# OBDadapter.net
KiCad netlist of a schematic drawn in EAGLE
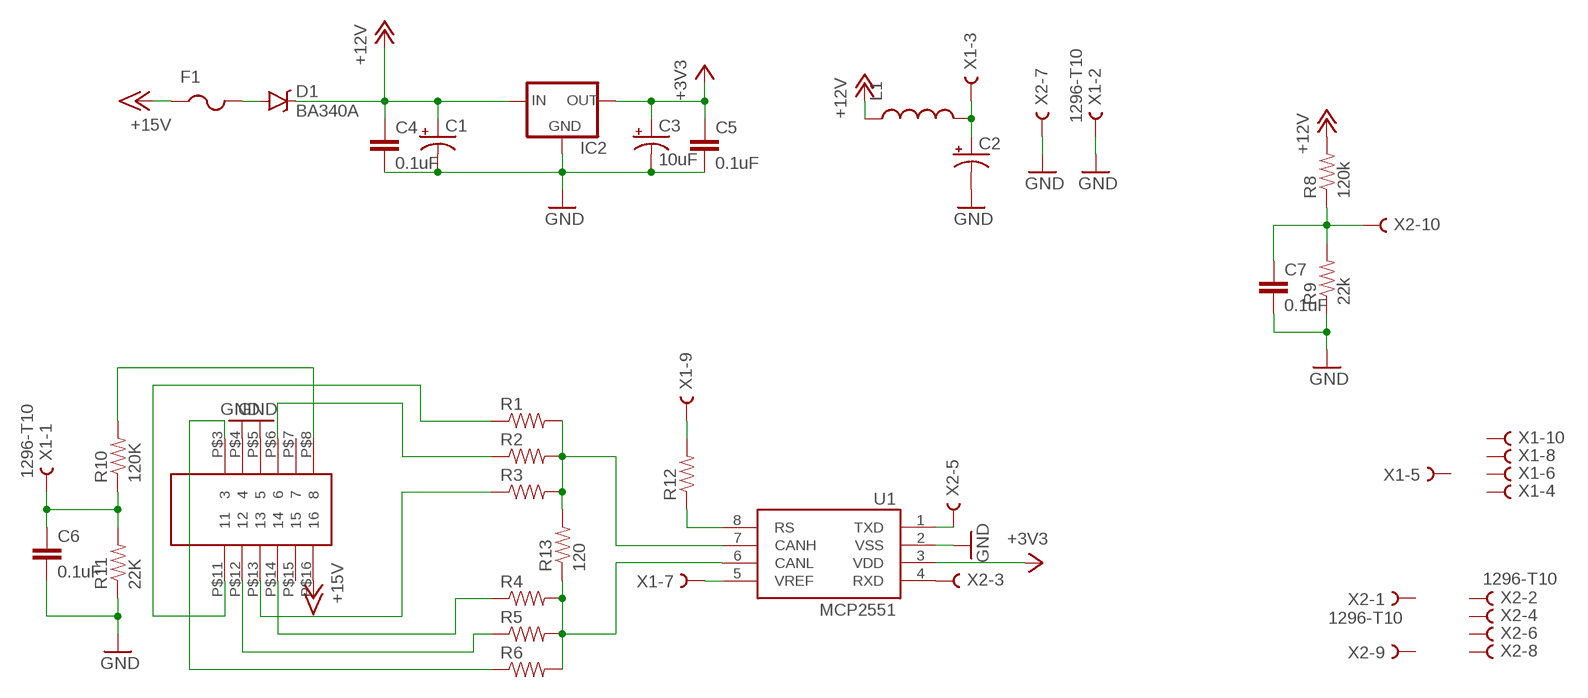
[diagram p0: schematic, sheet 1]

(export (version "E")
  (design (tool "Eeschema 10.0.6"))
  (components
    (comp (ref "C1")
      (value "CAP_POL3528-KIT")
      (footprint "eagle-import:EIA3528-KIT")
      (libsource (lib "eagle-import") (part "CAP_POL3528-KIT"))
    )
    (comp (ref "C2")
      (value "CAP_POL6032")
      (footprint "eagle-import:EIA6032")
      (libsource (lib "eagle-import") (part "CAP_POL6032"))
    )
    (comp (ref "C3")
      (value "10uF")
      (footprint "eagle-import:EIA3528")
      (libsource (lib "eagle-import") (part "10UF-20V-10%(TANT)"))
    )
    (comp (ref "C4")
      (value "0.1uF")
      (footprint "eagle-import:0603-CAP")
      (libsource (lib "eagle-import") (part "0.1UF-25V(+80/-20%)(0603)"))
    )
    (comp (ref "C5")
      (value "0.1uF")
      (footprint "eagle-import:0603-CAP")
      (libsource (lib "eagle-import") (part "0.1UF-25V(+80/-20%)(0603)"))
    )
    (comp (ref "C6")
      (value "0.1uF")
      (footprint "eagle-import:0603-CAP")
      (libsource (lib "eagle-import") (part "0.1UF-25V(+80/-20%)(0603)"))
    )
    (comp (ref "C7")
      (value "0.1uF")
      (footprint "eagle-import:0603-CAP")
      (libsource (lib "eagle-import") (part "0.1UF-25V(+80/-20%)(0603)"))
    )
    (comp (ref "D1")
      (value "BA340A")
      (footprint "eagle-import:SMA-DIODE")
      (libsource (lib "eagle-import") (part "B340A"))
    )
    (comp (ref "F1")
      (value "PTCFUSE-1206")
      (footprint "eagle-import:R1206")
      (libsource (lib "eagle-import") (part "PTCFUSE-1206"))
    )
    (comp (ref "IC2")
      (value "V_REG_78XXSOT89")
      (footprint "eagle-import:SOT89")
      (libsource (lib "eagle-import") (part "V_REG_78XXSOT89"))
    )
    (comp (ref "L1")
      (value "INDUCTOR1210")
      (footprint "eagle-import:1210")
      (libsource (lib "eagle-import") (part "INDUCTOR1210"))
    )
    (comp (ref "R1")
      (value "RESISTOR0805-RES")
      (footprint "eagle-import:0805")
      (libsource (lib "eagle-import") (part "RESISTOR0805-RES"))
    )
    (comp (ref "R2")
      (value "RESISTOR0805-RES")
      (footprint "eagle-import:0805")
      (libsource (lib "eagle-import") (part "RESISTOR0805-RES"))
    )
    (comp (ref "R3")
      (value "RESISTOR0805-RES")
      (footprint "eagle-import:0805")
      (libsource (lib "eagle-import") (part "RESISTOR0805-RES"))
    )
    (comp (ref "R4")
      (value "RESISTOR0805-RES")
      (footprint "eagle-import:0805")
      (libsource (lib "eagle-import") (part "RESISTOR0805-RES"))
    )
    (comp (ref "R5")
      (value "RESISTOR0805-RES")
      (footprint "eagle-import:0805")
      (libsource (lib "eagle-import") (part "RESISTOR0805-RES"))
    )
    (comp (ref "R6")
      (value "RESISTOR0805-RES")
      (footprint "eagle-import:0805")
      (libsource (lib "eagle-import") (part "RESISTOR0805-RES"))
    )
    (comp (ref "R8")
      (value "120k")
      (footprint "eagle-import:0805")
      (libsource (lib "eagle-import") (part "RESISTOR0805-RES"))
    )
    (comp (ref "R9")
      (value "22k")
      (footprint "eagle-import:0805")
      (libsource (lib "eagle-import") (part "RESISTOR0805-RES"))
    )
    (comp (ref "R10")
      (value "120K")
      (footprint "eagle-import:0805")
      (libsource (lib "eagle-import") (part "RESISTOR0805-RES"))
    )
    (comp (ref "R11")
      (value "22K")
      (footprint "eagle-import:0805")
      (libsource (lib "eagle-import") (part "RESISTOR0805-RES"))
    )
    (comp (ref "R12")
      (value "RESISTOR0805-RES")
      (footprint "eagle-import:0805")
      (libsource (lib "eagle-import") (part "RESISTOR0805-RES"))
    )
    (comp (ref "R13")
      (value "120")
      (footprint "eagle-import:0805")
      (libsource (lib "eagle-import") (part "RESISTOR0805-RES"))
    )
    (comp (ref "U$1")
      (value "OBD-4")
      (footprint "eagle-import:OBD-4")
      (libsource (lib "eagle-import") (part "OBD-4"))
    )
    (comp (ref "U1")
      (value "MCP2551")
      (footprint "eagle-import:SO08")
      (libsource (lib "eagle-import") (part "MCP2551"))
    )
    (comp (ref "X1")
      (value "1296-T10")
      (footprint "eagle-import:1296-10")
      (libsource (lib "eagle-import") (part "1296-T10"))
    )
    (comp (ref "X2")
      (value "1296-T10")
      (footprint "eagle-import:1296-10")
      (libsource (lib "eagle-import") (part "1296-T10"))
    )
  )
  (nets
    (net (code "1") (name "+3V3") (class "Default")
      (node (ref "C3") (pin "A") (pinfunction "+_A") (pintype "passive"))
      (node (ref "C5") (pin "1") (pinfunction "1_1") (pintype "passive"))
      (node (ref "IC2") (pin "1") (pinfunction "OUT_1") (pintype "output"))
      (node (ref "U1") (pin "3") (pinfunction "VDD_3") (pintype "bidirectional"))
    )
    (net (code "2") (name "+12V") (class "Default")
      (node (ref "C1") (pin "A") (pinfunction "+_A") (pintype "passive"))
      (node (ref "C4") (pin "1") (pinfunction "1_1") (pintype "passive"))
      (node (ref "D1") (pin "C") (pinfunction "C_C") (pintype "passive"))
      (node (ref "IC2") (pin "3") (pinfunction "IN_3") (pintype "input"))
      (node (ref "L1") (pin "1") (pinfunction "1_1") (pintype "passive"))
      (node (ref "R8") (pin "2") (pinfunction "2_2") (pintype "passive"))
    )
    (net (code "3") (name "+15V") (class "Default")
      (node (ref "F1") (pin "1") (pinfunction "1_1") (pintype "passive"))
      (node (ref "U$1") (pin "P$16") (pinfunction "16_P$16") (pintype "bidirectional"))
    )
    (net (code "4") (name "GND") (class "Default")
      (node (ref "C1") (pin "C") (pinfunction "-_C") (pintype "passive"))
      (node (ref "C2") (pin "P$2") (pinfunction "-_P$2") (pintype "passive"))
      (node (ref "C3") (pin "C") (pinfunction "-_C") (pintype "passive"))
      (node (ref "C4") (pin "2") (pinfunction "2_2") (pintype "passive"))
      (node (ref "C5") (pin "2") (pinfunction "2_2") (pintype "passive"))
      (node (ref "C6") (pin "2") (pinfunction "2_2") (pintype "passive"))
      (node (ref "C7") (pin "2") (pinfunction "2_2") (pintype "passive"))
      (node (ref "IC2") (pin "2") (pinfunction "GND_2") (pintype "input"))
      (node (ref "IC2") (pin "4") (pinfunction "GND_4") (pintype "input"))
      (node (ref "R11") (pin "1") (pinfunction "1_1") (pintype "passive"))
      (node (ref "R9") (pin "1") (pinfunction "1_1") (pintype "passive"))
      (node (ref "U$1") (pin "P$4") (pinfunction "4_P$4") (pintype "bidirectional"))
      (node (ref "U$1") (pin "P$5") (pinfunction "5_P$5") (pintype "bidirectional"))
      (node (ref "U1") (pin "2") (pinfunction "VSS_2") (pintype "bidirectional"))
      (node (ref "X1") (pin "2") (pinfunction "B_2") (pintype "passive"))
      (node (ref "X2") (pin "7") (pinfunction "B_7") (pintype "passive"))
    )
    (net (code "5") (name "Net-(C2-+)") (class "Default")
      (node (ref "C2") (pin "P$1") (pinfunction "+_P$1") (pintype "passive"))
      (node (ref "L1") (pin "2") (pinfunction "2_2") (pintype "passive"))
      (node (ref "X1") (pin "3") (pinfunction "B_3") (pintype "passive"))
    )
    (net (code "6") (name "Net-(D1-PadA)") (class "Default")
      (node (ref "D1") (pin "A") (pinfunction "A_A") (pintype "passive"))
      (node (ref "F1") (pin "2") (pinfunction "2_2") (pintype "passive"))
    )
    (net (code "7") (name "Net-(U$1-3)") (class "Default")
      (node (ref "R6") (pin "1") (pinfunction "1_1") (pintype "passive"))
      (node (ref "U$1") (pin "P$3") (pinfunction "3_P$3") (pintype "bidirectional"))
    )
    (net (code "8") (name "Net-(U$1-6)") (class "Default")
      (node (ref "R2") (pin "1") (pinfunction "1_1") (pintype "passive"))
      (node (ref "U$1") (pin "P$6") (pinfunction "6_P$6") (pintype "bidirectional"))
    )
    (net (code "9") (name "Net-(U$1-8)") (class "Default")
      (node (ref "R10") (pin "2") (pinfunction "2_2") (pintype "passive"))
      (node (ref "U$1") (pin "P$8") (pinfunction "8_P$8") (pintype "bidirectional"))
    )
    (net (code "10") (name "Net-(U$1-11)") (class "Default")
      (node (ref "R1") (pin "1") (pinfunction "1_1") (pintype "passive"))
      (node (ref "U$1") (pin "P$11") (pinfunction "11_P$11") (pintype "bidirectional"))
    )
    (net (code "11") (name "Net-(U$1-12)") (class "Default")
      (node (ref "R5") (pin "1") (pinfunction "1_1") (pintype "passive"))
      (node (ref "U$1") (pin "P$12") (pinfunction "12_P$12") (pintype "bidirectional"))
    )
    (net (code "12") (name "Net-(U$1-13)") (class "Default")
      (node (ref "R3") (pin "1") (pinfunction "1_1") (pintype "passive"))
      (node (ref "U$1") (pin "P$13") (pinfunction "13_P$13") (pintype "bidirectional"))
    )
    (net (code "13") (name "Net-(U$1-14)") (class "Default")
      (node (ref "R4") (pin "1") (pinfunction "1_1") (pintype "passive"))
      (node (ref "U$1") (pin "P$14") (pinfunction "14_P$14") (pintype "bidirectional"))
    )
    (net (code "14") (name "Net-(U1-CANH)") (class "Default")
      (node (ref "R1") (pin "2") (pinfunction "2_2") (pintype "passive"))
      (node (ref "R13") (pin "2") (pinfunction "2_2") (pintype "passive"))
      (node (ref "R2") (pin "2") (pinfunction "2_2") (pintype "passive"))
      (node (ref "R3") (pin "2") (pinfunction "2_2") (pintype "passive"))
      (node (ref "U1") (pin "7") (pinfunction "CANH_7") (pintype "bidirectional"))
    )
    (net (code "15") (name "Net-(U1-CANL)") (class "Default")
      (node (ref "R13") (pin "1") (pinfunction "1_1") (pintype "passive"))
      (node (ref "R4") (pin "2") (pinfunction "2_2") (pintype "passive"))
      (node (ref "R5") (pin "2") (pinfunction "2_2") (pintype "passive"))
      (node (ref "R6") (pin "2") (pinfunction "2_2") (pintype "passive"))
      (node (ref "U1") (pin "6") (pinfunction "CANL_6") (pintype "bidirectional"))
    )
    (net (code "16") (name "Net-(U1-RS)") (class "Default")
      (node (ref "R12") (pin "1") (pinfunction "1_1") (pintype "passive"))
      (node (ref "U1") (pin "8") (pinfunction "RS_8") (pintype "bidirectional"))
    )
    (net (code "17") (name "Net-(U1-RXD)") (class "Default")
      (node (ref "U1") (pin "4") (pinfunction "RXD_4") (pintype "bidirectional"))
      (node (ref "X2") (pin "3") (pinfunction "B_3") (pintype "passive"))
    )
    (net (code "18") (name "Net-(U1-TXD)") (class "Default")
      (node (ref "U1") (pin "1") (pinfunction "TXD_1") (pintype "bidirectional"))
      (node (ref "X2") (pin "5") (pinfunction "B_5") (pintype "passive"))
    )
    (net (code "19") (name "Net-(U1-VREF)") (class "Default")
      (node (ref "U1") (pin "5") (pinfunction "VREF_5") (pintype "bidirectional"))
      (node (ref "X1") (pin "7") (pinfunction "B_7") (pintype "passive"))
    )
    (net (code "20") (name "Net-(X1A-B)") (class "Default")
      (node (ref "C6") (pin "1") (pinfunction "1_1") (pintype "passive"))
      (node (ref "R10") (pin "1") (pinfunction "1_1") (pintype "passive"))
      (node (ref "R11") (pin "2") (pinfunction "2_2") (pintype "passive"))
      (node (ref "X1") (pin "1") (pinfunction "B_1") (pintype "passive"))
    )
    (net (code "21") (name "Net-(X1J-B)") (class "Default")
      (node (ref "R12") (pin "2") (pinfunction "2_2") (pintype "passive"))
      (node (ref "X1") (pin "9") (pinfunction "B_9") (pintype "passive"))
    )
    (net (code "22") (name "Net-(X2B-B)") (class "Default")
      (node (ref "C7") (pin "1") (pinfunction "1_1") (pintype "passive"))
      (node (ref "R8") (pin "1") (pinfunction "1_1") (pintype "passive"))
      (node (ref "R9") (pin "2") (pinfunction "2_2") (pintype "passive"))
      (node (ref "X2") (pin "10") (pinfunction "B_10") (pintype "passive"))
    )
    (net (code "23") (name "unconnected-(U$1-7-PadP$7)") (class "Default")
      (node (ref "U$1") (pin "P$7") (pinfunction "7_P$7") (pintype "bidirectional"))
    )
    (net (code "24") (name "unconnected-(U$1-15-PadP$15)") (class "Default")
      (node (ref "U$1") (pin "P$15") (pinfunction "15_P$15") (pintype "bidirectional"))
    )
    (net (code "25") (name "unconnected-(X1B-B-Pad10)") (class "Default")
      (node (ref "X1") (pin "10") (pinfunction "B_10") (pintype "passive"))
    )
    (net (code "26") (name "unconnected-(X1E-B-Pad4)") (class "Default")
      (node (ref "X1") (pin "4") (pinfunction "B_4") (pintype "passive"))
    )
    (net (code "27") (name "unconnected-(X1F-B-Pad5)") (class "Default")
      (node (ref "X1") (pin "5") (pinfunction "B_5") (pintype "passive"))
    )
    (net (code "28") (name "unconnected-(X1G-B-Pad6)") (class "Default")
      (node (ref "X1") (pin "6") (pinfunction "B_6") (pintype "passive"))
    )
    (net (code "29") (name "unconnected-(X1I-B-Pad8)") (class "Default")
      (node (ref "X1") (pin "8") (pinfunction "B_8") (pintype "passive"))
    )
    (net (code "30") (name "unconnected-(X2A-B-Pad1)") (class "Default")
      (node (ref "X2") (pin "1") (pinfunction "B_1") (pintype "passive"))
    )
    (net (code "31") (name "unconnected-(X2C-B-Pad2)") (class "Default")
      (node (ref "X2") (pin "2") (pinfunction "B_2") (pintype "passive"))
    )
    (net (code "32") (name "unconnected-(X2E-B-Pad4)") (class "Default")
      (node (ref "X2") (pin "4") (pinfunction "B_4") (pintype "passive"))
    )
    (net (code "33") (name "unconnected-(X2G-B-Pad6)") (class "Default")
      (node (ref "X2") (pin "6") (pinfunction "B_6") (pintype "passive"))
    )
    (net (code "34") (name "unconnected-(X2I-B-Pad8)") (class "Default")
      (node (ref "X2") (pin "8") (pinfunction "B_8") (pintype "passive"))
    )
    (net (code "35") (name "unconnected-(X2J-B-Pad9)") (class "Default")
      (node (ref "X2") (pin "9") (pinfunction "B_9") (pintype "passive"))
    )
  )
)
